# soldering_is_easy.net
KiCad netlist of a schematic drawn in EAGLE
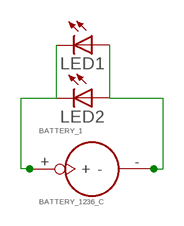
[diagram p0: schematic, sheet 1]

(export (version "E")
  (design (tool "Eeschema 10.0.6"))
  (components
    (comp (ref "BATTERY_1")
      (value "BATTERY_1236_C")
      (footprint "eagle-import:BATTERY_1236_C")
      (libsource (lib "eagle-import") (part "BATTERY_1236_C"))
    )
    (comp (ref "LED1")
      (value "LED5MM")
      (footprint "eagle-import:LED5MM")
      (libsource (lib "eagle-import") (part "LED5MM"))
    )
    (comp (ref "LED2")
      (value "LED5MM")
      (footprint "eagle-import:LED5MM")
      (libsource (lib "eagle-import") (part "LED5MM"))
    )
  )
  (nets
    (net (code "1") (name "Net-(BATTERY_1-Pad-)") (class "Default")
      (node (ref "BATTERY_1") (pin "-") (pinfunction "-_-") (pintype "bidirectional"))
      (node (ref "LED1") (pin "A") (pinfunction "A_A") (pintype "passive"))
      (node (ref "LED2") (pin "A") (pinfunction "A_A") (pintype "passive"))
    )
    (net (code "2") (name "Net-(LED1-C)") (class "Default")
      (node (ref "BATTERY_1") (pin "+") (pinfunction "+_+") (pintype "bidirectional"))
      (node (ref "LED1") (pin "K") (pinfunction "C_K") (pintype "passive"))
      (node (ref "LED2") (pin "K") (pinfunction "C_K") (pintype "passive"))
    )
  )
)
